# PS_TPS54340_Voltage_CurrentRev2_1.net
KiCad netlist of a schematic drawn in EAGLE
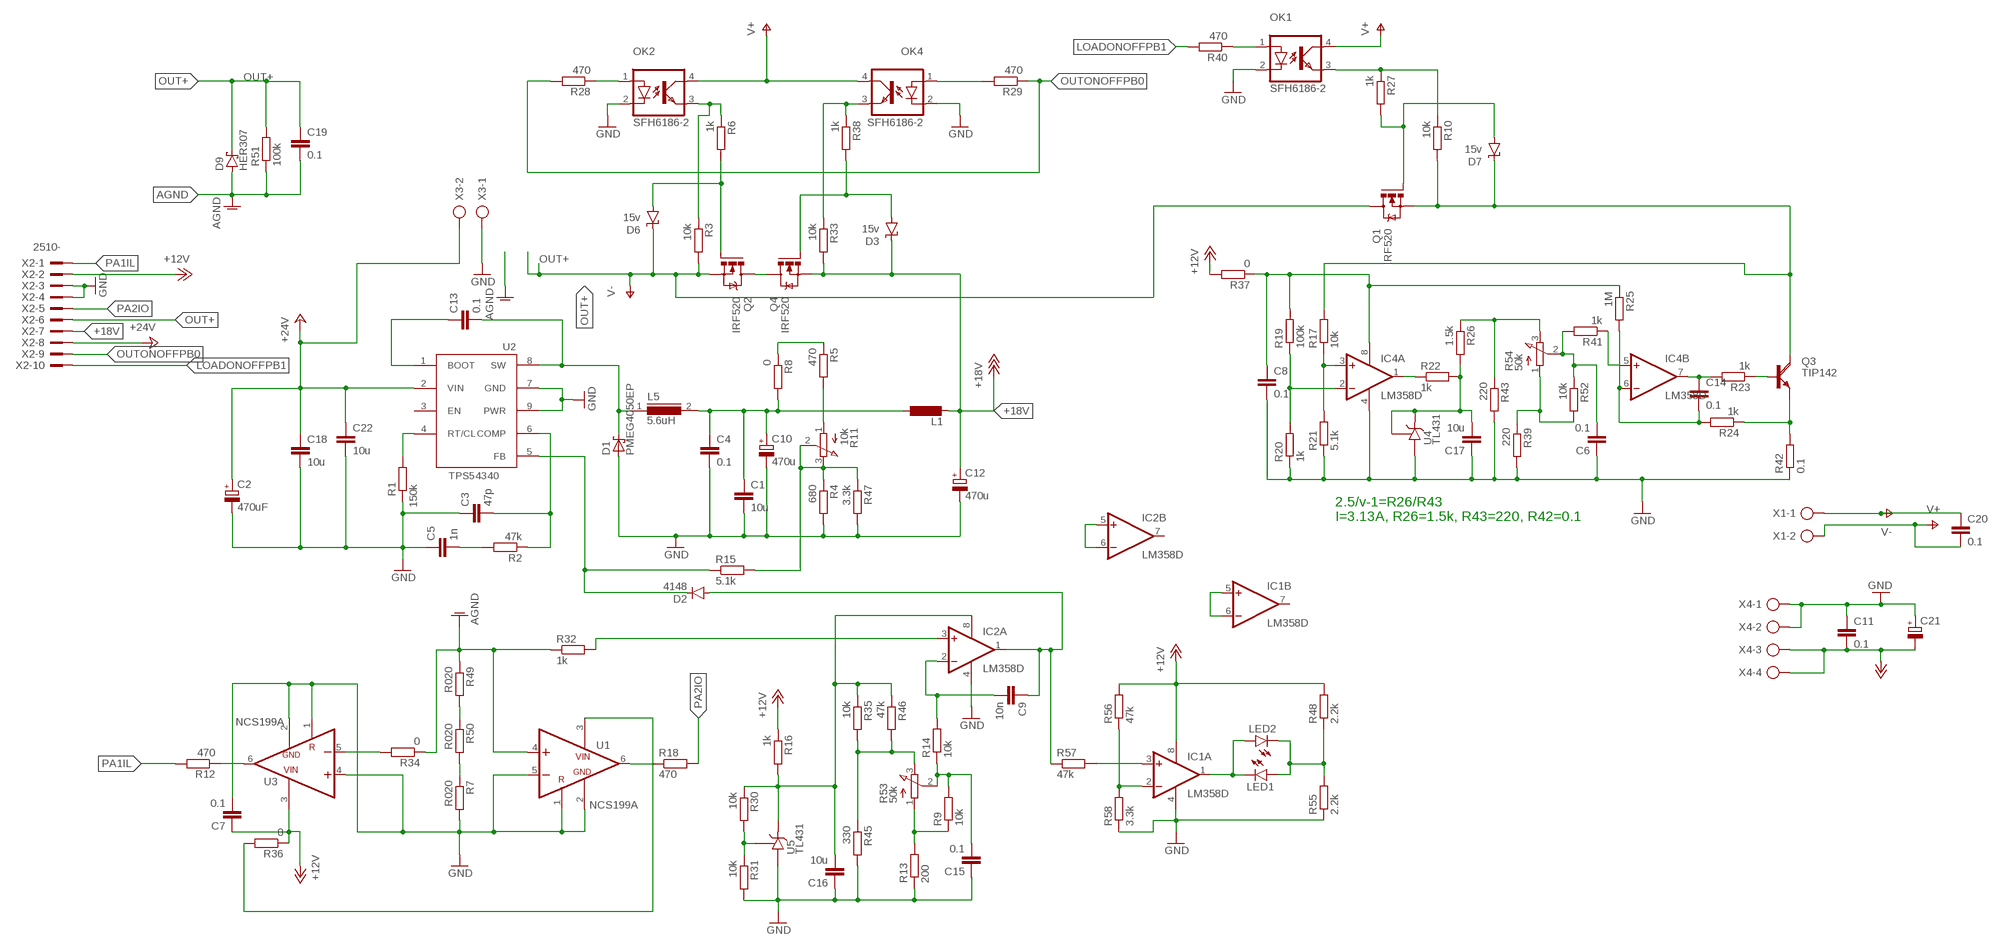
[diagram p0: schematic, sheet 1]

(export (version "E")
  (design (tool "Eeschema 10.0.6"))
  (components
    (comp (ref "C1")
      (value "10u")
      (footprint "eagle-import:C1210")
      (libsource (lib "eagle-import") (part "rcl_334_C-EUC1210"))
    )
    (comp (ref "C2")
      (value "470uF")
      (footprint "eagle-import:E5-10,5")
      (libsource (lib "eagle-import") (part "CPOL-EUE5-10.5"))
    )
    (comp (ref "C3")
      (value "47p")
      (footprint "eagle-import:C0603K")
      (libsource (lib "eagle-import") (part "rcl_334_C-EUC0603K"))
    )
    (comp (ref "C4")
      (value "0.1")
      (footprint "eagle-import:C1206")
      (libsource (lib "eagle-import") (part "C-EUC1206"))
    )
    (comp (ref "C5")
      (value "1n")
      (footprint "eagle-import:C0603K")
      (libsource (lib "eagle-import") (part "rcl_334_C-EUC0603K"))
    )
    (comp (ref "C6")
      (value "0.1")
      (footprint "eagle-import:C0603K")
      (libsource (lib "eagle-import") (part "rcl_334_C-EUC0603K"))
    )
    (comp (ref "C7")
      (value "0.1")
      (footprint "eagle-import:C0603K")
      (libsource (lib "eagle-import") (part "rcl_334_C-EUC0603K"))
    )
    (comp (ref "C8")
      (value "0.1")
      (footprint "eagle-import:C1206")
      (libsource (lib "eagle-import") (part "C-EUC1206"))
    )
    (comp (ref "C9")
      (value "10n")
      (footprint "eagle-import:C0603K")
      (libsource (lib "eagle-import") (part "rcl_334_C-EUC0603K"))
    )
    (comp (ref "C10")
      (value "470u")
      (footprint "eagle-import:E5-10,5")
      (libsource (lib "eagle-import") (part "CPOL-EUE5-10.5"))
    )
    (comp (ref "C11")
      (value "0.1")
      (footprint "eagle-import:C1206")
      (libsource (lib "eagle-import") (part "C-EUC1206"))
    )
    (comp (ref "C12")
      (value "470u")
      (footprint "eagle-import:E5-10,5")
      (libsource (lib "eagle-import") (part "CPOL-EUE5-10.5"))
    )
    (comp (ref "C13")
      (value "0.1")
      (footprint "eagle-import:C102-043X133")
      (libsource (lib "eagle-import") (part "rcl_334_C-EU102-043X133"))
    )
    (comp (ref "C14")
      (value "0.1")
      (footprint "eagle-import:C1206")
      (libsource (lib "eagle-import") (part "C-EUC1206"))
    )
    (comp (ref "C15")
      (value "0.1")
      (footprint "eagle-import:C0603K")
      (libsource (lib "eagle-import") (part "rcl_334_C-EUC0603K"))
    )
    (comp (ref "C16")
      (value "10u")
      (footprint "eagle-import:C0603K")
      (libsource (lib "eagle-import") (part "rcl_334_C-EUC0603K"))
    )
    (comp (ref "C17")
      (value "10u")
      (footprint "eagle-import:C0603K")
      (libsource (lib "eagle-import") (part "rcl_334_C-EUC0603K"))
    )
    (comp (ref "C18")
      (value "10u")
      (footprint "eagle-import:C1210")
      (libsource (lib "eagle-import") (part "rcl_334_C-EUC1210"))
    )
    (comp (ref "C19")
      (value "0.1")
      (footprint "eagle-import:C150-054X183")
      (libsource (lib "eagle-import") (part "rcl_334_C-EU150-054X183"))
    )
    (comp (ref "C20")
      (value "0.1")
      (footprint "eagle-import:C1206")
      (libsource (lib "eagle-import") (part "C-EUC1206"))
    )
    (comp (ref "C21")
      (value "CPOL-EUE2.5-6")
      (footprint "eagle-import:E2,5-6")
      (libsource (lib "eagle-import") (part "CPOL-EUE2.5-6"))
    )
    (comp (ref "C22")
      (value "10u")
      (footprint "eagle-import:C1210")
      (libsource (lib "eagle-import") (part "rcl_334_C-EUC1210"))
    )
    (comp (ref "D1")
      (value "PMEG4050EP")
      (footprint "eagle-import:SOD128")
      (libsource (lib "eagle-import") (part "PMEG4050EP"))
    )
    (comp (ref "D2")
      (value "4148")
      (footprint "eagle-import:SOD80C")
      (libsource (lib "eagle-import") (part "PMLL41SOD80C"))
    )
    (comp (ref "D3")
      (value "15v")
      (footprint "eagle-import:SMBJ")
      (libsource (lib "eagle-import") (part "SUPPRESSOR-SMBJ"))
    )
    (comp (ref "D6")
      (value "15v")
      (footprint "eagle-import:SMBJ")
      (libsource (lib "eagle-import") (part "SUPPRESSOR-SMBJ"))
    )
    (comp (ref "D7")
      (value "15v")
      (footprint "eagle-import:SMBJ")
      (libsource (lib "eagle-import") (part "SUPPRESSOR-SMBJ"))
    )
    (comp (ref "D9")
      (value "HER307")
      (footprint "eagle-import:CB429-17")
      (libsource (lib "eagle-import") (part "15KEXX"))
    )
    (comp (ref "IC1")
      (value "LM358D")
      (footprint "eagle-import:SO08")
      (libsource (lib "eagle-import") (part "LM358D"))
    )
    (comp (ref "IC2")
      (value "LM358D")
      (footprint "eagle-import:SO08")
      (libsource (lib "eagle-import") (part "LM358D"))
    )
    (comp (ref "IC4")
      (value "LM358D")
      (footprint "eagle-import:SO08")
      (libsource (lib "eagle-import") (part "LM358D"))
    )
    (comp (ref "L1")
      (value "L-EU0207/5V")
      (footprint "eagle-import:0207_5V")
      (libsource (lib "eagle-import") (part "L-EU0207/5V"))
    )
    (comp (ref "L5")
      (value "5.6uH")
      (footprint "eagle-import:DR125")
      (libsource (lib "eagle-import") (part "DR125"))
    )
    (comp (ref "LED1")
      (value "LEDB152")
      (footprint "eagle-import:Q62902-B152")
      (libsource (lib "eagle-import") (part "LEDB152"))
    )
    (comp (ref "LED2")
      (value "LEDB152")
      (footprint "eagle-import:Q62902-B152")
      (libsource (lib "eagle-import") (part "LEDB152"))
    )
    (comp (ref "OK1")
      (value "SFH6186-2")
      (footprint "eagle-import:SMD4-7")
      (fields (field (name "MF") "VISHAY/TELEFUNKEN"))
      (libsource (lib "eagle-import") (part "SFH618?6-2"))
    )
    (comp (ref "OK2")
      (value "SFH6186-2")
      (footprint "eagle-import:SMD4-7")
      (fields (field (name "MF") "VISHAY/TELEFUNKEN"))
      (libsource (lib "eagle-import") (part "SFH618?6-2"))
    )
    (comp (ref "OK4")
      (value "SFH6186-2")
      (footprint "eagle-import:SMD4-7")
      (fields (field (name "MF") "VISHAY/TELEFUNKEN"))
      (libsource (lib "eagle-import") (part "SFH618?6-2"))
    )
    (comp (ref "Q1")
      (value "IRF520")
      (footprint "eagle-import:TO220BV")
      (libsource (lib "eagle-import") (part "IRF520"))
    )
    (comp (ref "Q2")
      (value "IRF520")
      (footprint "eagle-import:TO220BV")
      (libsource (lib "eagle-import") (part "IRF520"))
    )
    (comp (ref "Q3")
      (value "TIP142")
      (footprint "eagle-import:SOT93")
      (libsource (lib "eagle-import") (part "TIP142"))
    )
    (comp (ref "Q4")
      (value "IRF520")
      (footprint "eagle-import:TO220BV")
      (libsource (lib "eagle-import") (part "IRF520"))
    )
    (comp (ref "R1")
      (value "150k")
      (footprint "eagle-import:R1206")
      (libsource (lib "eagle-import") (part "R-EU_R1206"))
    )
    (comp (ref "R2")
      (value "47k")
      (footprint "eagle-import:R0603")
      (libsource (lib "eagle-import") (part "rcl_334_R-EU_R0603"))
    )
    (comp (ref "R3")
      (value "10k")
      (footprint "eagle-import:R0603")
      (libsource (lib "eagle-import") (part "rcl_334_R-EU_R0603"))
    )
    (comp (ref "R4")
      (value "680")
      (footprint "eagle-import:R1206")
      (libsource (lib "eagle-import") (part "R-EU_R1206"))
    )
    (comp (ref "R5")
      (value "470")
      (footprint "eagle-import:R1206")
      (libsource (lib "eagle-import") (part "R-EU_R1206"))
    )
    (comp (ref "R6")
      (value "1k")
      (footprint "eagle-import:R0603")
      (libsource (lib "eagle-import") (part "rcl_334_R-EU_R0603"))
    )
    (comp (ref "R7")
      (value "R020")
      (footprint "eagle-import:R1206")
      (libsource (lib "eagle-import") (part "R-EU_R1206"))
    )
    (comp (ref "R8")
      (value "0")
      (footprint "eagle-import:R0603")
      (libsource (lib "eagle-import") (part "rcl_334_R-EU_R0603"))
    )
    (comp (ref "R9")
      (value "10k")
      (footprint "eagle-import:R0603")
      (libsource (lib "eagle-import") (part "rcl_334_R-EU_R0603"))
    )
    (comp (ref "R10")
      (value "10k")
      (footprint "eagle-import:R0603")
      (libsource (lib "eagle-import") (part "rcl_334_R-EU_R0603"))
    )
    (comp (ref "R11")
      (value "10k")
      (footprint "eagle-import:3RP_1610N")
      (libsource (lib "eagle-import") (part "3RP/1610N"))
    )
    (comp (ref "R12")
      (value "470")
      (footprint "eagle-import:R0603")
      (libsource (lib "eagle-import") (part "rcl_334_R-EU_R0603"))
    )
    (comp (ref "R13")
      (value "200")
      (footprint "eagle-import:R0603")
      (libsource (lib "eagle-import") (part "rcl_334_R-EU_R0603"))
    )
    (comp (ref "R14")
      (value "10k")
      (footprint "eagle-import:R1206")
      (libsource (lib "eagle-import") (part "R-EU_R1206"))
    )
    (comp (ref "R15")
      (value "5.1k")
      (footprint "eagle-import:R0603")
      (libsource (lib "eagle-import") (part "rcl_334_R-EU_R0603"))
    )
    (comp (ref "R16")
      (value "1k")
      (footprint "eagle-import:R0603")
      (libsource (lib "eagle-import") (part "rcl_334_R-EU_R0603"))
    )
    (comp (ref "R17")
      (value "10k")
      (footprint "eagle-import:R1206")
      (libsource (lib "eagle-import") (part "R-EU_R1206"))
    )
    (comp (ref "R18")
      (value "470")
      (footprint "eagle-import:R0603")
      (libsource (lib "eagle-import") (part "rcl_334_R-EU_R0603"))
    )
    (comp (ref "R19")
      (value "100k")
      (footprint "eagle-import:R1206")
      (libsource (lib "eagle-import") (part "R-EU_R1206"))
    )
    (comp (ref "R20")
      (value "1k")
      (footprint "eagle-import:R1206")
      (libsource (lib "eagle-import") (part "R-EU_R1206"))
    )
    (comp (ref "R21")
      (value "5.1k")
      (footprint "eagle-import:R1206")
      (libsource (lib "eagle-import") (part "R-EU_R1206"))
    )
    (comp (ref "R22")
      (value "1k")
      (footprint "eagle-import:R0603")
      (libsource (lib "eagle-import") (part "rcl_334_R-EU_R0603"))
    )
    (comp (ref "R23")
      (value "1k")
      (footprint "eagle-import:R1206")
      (libsource (lib "eagle-import") (part "R-EU_R1206"))
    )
    (comp (ref "R24")
      (value "1k")
      (footprint "eagle-import:R1206")
      (libsource (lib "eagle-import") (part "R-EU_R1206"))
    )
    (comp (ref "R25")
      (value "1M")
      (footprint "eagle-import:R1206")
      (libsource (lib "eagle-import") (part "R-EU_R1206"))
    )
    (comp (ref "R26")
      (value "1.5k")
      (footprint "eagle-import:R0603")
      (libsource (lib "eagle-import") (part "rcl_334_R-EU_R0603"))
    )
    (comp (ref "R27")
      (value "1k")
      (footprint "eagle-import:R0603")
      (libsource (lib "eagle-import") (part "rcl_334_R-EU_R0603"))
    )
    (comp (ref "R28")
      (value "470")
      (footprint "eagle-import:R0603")
      (libsource (lib "eagle-import") (part "rcl_334_R-EU_R0603"))
    )
    (comp (ref "R29")
      (value "470")
      (footprint "eagle-import:R0603")
      (libsource (lib "eagle-import") (part "rcl_334_R-EU_R0603"))
    )
    (comp (ref "R30")
      (value "10k")
      (footprint "eagle-import:R0603")
      (libsource (lib "eagle-import") (part "rcl_334_R-EU_R0603"))
    )
    (comp (ref "R31")
      (value "10k")
      (footprint "eagle-import:R0603")
      (libsource (lib "eagle-import") (part "rcl_334_R-EU_R0603"))
    )
    (comp (ref "R32")
      (value "1k")
      (footprint "eagle-import:R1206")
      (libsource (lib "eagle-import") (part "R-EU_R1206"))
    )
    (comp (ref "R33")
      (value "10k")
      (footprint "eagle-import:R0603")
      (libsource (lib "eagle-import") (part "rcl_334_R-EU_R0603"))
    )
    (comp (ref "R34")
      (value "0")
      (footprint "eagle-import:R1206")
      (libsource (lib "eagle-import") (part "R-EU_R1206"))
    )
    (comp (ref "R35")
      (value "10k")
      (footprint "eagle-import:R0603")
      (libsource (lib "eagle-import") (part "rcl_334_R-EU_R0603"))
    )
    (comp (ref "R36")
      (value "0")
      (footprint "eagle-import:R1206")
      (libsource (lib "eagle-import") (part "R-EU_R1206"))
    )
    (comp (ref "R37")
      (value "0")
      (footprint "eagle-import:R1206")
      (libsource (lib "eagle-import") (part "R-EU_R1206"))
    )
    (comp (ref "R38")
      (value "1k")
      (footprint "eagle-import:R0603")
      (libsource (lib "eagle-import") (part "rcl_334_R-EU_R0603"))
    )
    (comp (ref "R39")
      (value "220")
      (footprint "eagle-import:R0603")
      (libsource (lib "eagle-import") (part "rcl_334_R-EU_R0603"))
    )
    (comp (ref "R40")
      (value "470")
      (footprint "eagle-import:R0603")
      (libsource (lib "eagle-import") (part "rcl_334_R-EU_R0603"))
    )
    (comp (ref "R41")
      (value "1k")
      (footprint "eagle-import:R1206")
      (libsource (lib "eagle-import") (part "R-EU_R1206"))
    )
    (comp (ref "R42")
      (value "0.1")
      (footprint "eagle-import:0414_15")
      (libsource (lib "eagle-import") (part "rcl_334_R-EU_0414/15"))
    )
    (comp (ref "R43")
      (value "220")
      (footprint "eagle-import:R0603")
      (libsource (lib "eagle-import") (part "rcl_334_R-EU_R0603"))
    )
    (comp (ref "R45")
      (value "330")
      (footprint "eagle-import:R0603")
      (libsource (lib "eagle-import") (part "rcl_334_R-EU_R0603"))
    )
    (comp (ref "R46")
      (value "47k")
      (footprint "eagle-import:R0603")
      (libsource (lib "eagle-import") (part "rcl_334_R-EU_R0603"))
    )
    (comp (ref "R47")
      (value "3.3k")
      (footprint "eagle-import:R1206")
      (libsource (lib "eagle-import") (part "R-EU_R1206"))
    )
    (comp (ref "R48")
      (value "2.2k")
      (footprint "eagle-import:R0603")
      (libsource (lib "eagle-import") (part "rcl_334_R-EU_R0603"))
    )
    (comp (ref "R49")
      (value "R020")
      (footprint "eagle-import:R1206")
      (libsource (lib "eagle-import") (part "R-EU_R1206"))
    )
    (comp (ref "R50")
      (value "R020")
      (footprint "eagle-import:R1206")
      (libsource (lib "eagle-import") (part "R-EU_R1206"))
    )
    (comp (ref "R51")
      (value "100k")
      (footprint "eagle-import:0207_15")
      (libsource (lib "eagle-import") (part "rcl_334_R-EU_0207/15"))
    )
    (comp (ref "R52")
      (value "10k")
      (footprint "eagle-import:R0603")
      (libsource (lib "eagle-import") (part "rcl_334_R-EU_R0603"))
    )
    (comp (ref "R53")
      (value "50k")
      (footprint "eagle-import:3RP_1610N")
      (libsource (lib "eagle-import") (part "3RP/1610N"))
    )
    (comp (ref "R54")
      (value "50k")
      (footprint "eagle-import:3RP_1610N")
      (libsource (lib "eagle-import") (part "3RP/1610N"))
    )
    (comp (ref "R55")
      (value "2.2k")
      (footprint "eagle-import:R0603")
      (libsource (lib "eagle-import") (part "rcl_334_R-EU_R0603"))
    )
    (comp (ref "R56")
      (value "47k")
      (footprint "eagle-import:R0603")
      (libsource (lib "eagle-import") (part "rcl_334_R-EU_R0603"))
    )
    (comp (ref "R57")
      (value "47k")
      (footprint "eagle-import:R0603")
      (libsource (lib "eagle-import") (part "rcl_334_R-EU_R0603"))
    )
    (comp (ref "R58")
      (value "3.3k")
      (footprint "eagle-import:R0603")
      (libsource (lib "eagle-import") (part "rcl_334_R-EU_R0603"))
    )
    (comp (ref "U1")
      (value "NCS199A")
      (footprint "eagle-import:SOT363")
      (libsource (lib "eagle-import") (part "NCS199A"))
    )
    (comp (ref "U2")
      (value "TPS54340")
      (footprint "eagle-import:HSOP")
      (libsource (lib "eagle-import") (part "TPS54340SO8"))
    )
    (comp (ref "U3")
      (value "NCS199A")
      (footprint "eagle-import:SOT363")
      (libsource (lib "eagle-import") (part "NCS199A"))
    )
    (comp (ref "U4")
      (value "TL431")
      (footprint "eagle-import:SOT23")
      (libsource (lib "eagle-import") (part "TL431"))
    )
    (comp (ref "U5")
      (value "TL431")
      (footprint "eagle-import:SOT23")
      (libsource (lib "eagle-import") (part "TL431"))
    )
    (comp (ref "X1")
      (value "AK500/2")
      (footprint "eagle-import:AK500_2")
      (libsource (lib "eagle-import") (part "AK500/2"))
    )
    (comp (ref "X2")
      (value "2510-")
      (footprint "eagle-import:PAK100_2500-10")
      (fields (field (name "MF") "3M") (field (name "MPN") "2510-6002UB"))
      (libsource (lib "eagle-import") (part "2510-"))
    )
    (comp (ref "X3")
      (value "AK500/2")
      (footprint "eagle-import:AK500_2")
      (libsource (lib "eagle-import") (part "AK500/2"))
    )
    (comp (ref "X4")
      (value "AK500/4")
      (footprint "eagle-import:AK500_4")
      (libsource (lib "eagle-import") (part "AK500/4"))
    )
  )
  (nets
    (net (code "1") (name "+12V") (class "Default")
      (node (ref "C11") (pin "2") (pinfunction "2_2") (pintype "passive"))
      (node (ref "C21") (pin "-") (pinfunction "-_-") (pintype "passive"))
      (node (ref "C7") (pin "1") (pinfunction "1_1") (pintype "passive"))
      (node (ref "IC1") (pin "8") (pinfunction "V+_8") (pintype "power_in"))
      (node (ref "R16") (pin "1") (pinfunction "1_1") (pintype "passive"))
      (node (ref "R36") (pin "1") (pinfunction "1_1") (pintype "passive"))
      (node (ref "R37") (pin "2") (pinfunction "2_2") (pintype "passive"))
      (node (ref "R48") (pin "2") (pinfunction "2_2") (pintype "passive"))
      (node (ref "R56") (pin "2") (pinfunction "2_2") (pintype "passive"))
      (node (ref "U3") (pin "3") (pinfunction "VCC_3") (pintype "power_in"))
      (node (ref "X2") (pin "2") (pinfunction "KL_2") (pintype "passive"))
      (node (ref "X4") (pin "3") (pinfunction "KL_3") (pintype "passive"))
      (node (ref "X4") (pin "4") (pinfunction "KL_4") (pintype "passive"))
    )
    (net (code "2") (name "+18V") (class "Default")
      (node (ref "C12") (pin "+") (pinfunction "+_+") (pintype "passive"))
      (node (ref "D3") (pin "C") (pinfunction "C_C") (pintype "passive"))
      (node (ref "L1") (pin "2") (pinfunction "2_2") (pintype "passive"))
      (node (ref "Q4") (pin "S") (pinfunction "S_S") (pintype "passive"))
      (node (ref "R33") (pin "2") (pinfunction "2_2") (pintype "passive"))
      (node (ref "X2") (pin "7") (pinfunction "KL_7") (pintype "passive"))
    )
    (net (code "3") (name "+24V") (class "Default")
      (node (ref "C18") (pin "1") (pinfunction "1_1") (pintype "passive"))
      (node (ref "C2") (pin "+") (pinfunction "+_+") (pintype "passive"))
      (node (ref "C22") (pin "1") (pinfunction "1_1") (pintype "passive"))
      (node (ref "U2") (pin "2") (pinfunction "VIN_2") (pintype "power_in"))
      (node (ref "X2") (pin "8") (pinfunction "KL_8") (pintype "passive"))
      (node (ref "X3") (pin "2") (pinfunction "KL_2") (pintype "passive"))
    )
    (net (code "4") (name "AGND") (class "Default")
      (node (ref "C19") (pin "2") (pinfunction "2_2") (pintype "passive"))
      (node (ref "D9") (pin "A") (pinfunction "A_A") (pintype "passive"))
      (node (ref "R32") (pin "1") (pinfunction "1_1") (pintype "passive"))
      (node (ref "R34") (pin "1") (pinfunction "1_1") (pintype "passive"))
      (node (ref "R49") (pin "1") (pinfunction "1_1") (pintype "passive"))
      (node (ref "R51") (pin "1") (pinfunction "1_1") (pintype "passive"))
      (node (ref "U1") (pin "4") (pinfunction "IN+_4") (pintype "input"))
    )
    (net (code "5") (name "GND") (class "Default")
      (node (ref "C1") (pin "2") (pinfunction "2_2") (pintype "passive"))
      (node (ref "C10") (pin "-") (pinfunction "-_-") (pintype "passive"))
      (node (ref "C11") (pin "1") (pinfunction "1_1") (pintype "passive"))
      (node (ref "C12") (pin "-") (pinfunction "-_-") (pintype "passive"))
      (node (ref "C15") (pin "1") (pinfunction "1_1") (pintype "passive"))
      (node (ref "C16") (pin "1") (pinfunction "1_1") (pintype "passive"))
      (node (ref "C17") (pin "1") (pinfunction "1_1") (pintype "passive"))
      (node (ref "C18") (pin "2") (pinfunction "2_2") (pintype "passive"))
      (node (ref "C2") (pin "-") (pinfunction "-_-") (pintype "passive"))
      (node (ref "C21") (pin "+") (pinfunction "+_+") (pintype "passive"))
      (node (ref "C22") (pin "2") (pinfunction "2_2") (pintype "passive"))
      (node (ref "C3") (pin "1") (pinfunction "1_1") (pintype "passive"))
      (node (ref "C4") (pin "2") (pinfunction "2_2") (pintype "passive"))
      (node (ref "C5") (pin "1") (pinfunction "1_1") (pintype "passive"))
      (node (ref "C6") (pin "1") (pinfunction "1_1") (pintype "passive"))
      (node (ref "C7") (pin "2") (pinfunction "2_2") (pintype "passive"))
      (node (ref "C8") (pin "2") (pinfunction "2_2") (pintype "passive"))
      (node (ref "D1") (pin "2") (pinfunction "A_2") (pintype "passive"))
      (node (ref "IC1") (pin "4") (pinfunction "V-_4") (pintype "power_in"))
      (node (ref "IC2") (pin "4") (pinfunction "V-_4") (pintype "power_in"))
      (node (ref "IC4") (pin "4") (pinfunction "V-_4") (pintype "power_in"))
      (node (ref "OK1") (pin "2") (pinfunction "C_2") (pintype "passive"))
      (node (ref "OK2") (pin "2") (pinfunction "C_2") (pintype "passive"))
      (node (ref "OK4") (pin "2") (pinfunction "C_2") (pintype "passive"))
      (node (ref "R1") (pin "1") (pinfunction "1_1") (pintype "passive"))
      (node (ref "R13") (pin "1") (pinfunction "1_1") (pintype "passive"))
      (node (ref "R20") (pin "1") (pinfunction "1_1") (pintype "passive"))
      (node (ref "R21") (pin "1") (pinfunction "1_1") (pintype "passive"))
      (node (ref "R31") (pin "2") (pinfunction "2_2") (pintype "passive"))
      (node (ref "R39") (pin "2") (pinfunction "2_2") (pintype "passive"))
      (node (ref "R4") (pin "2") (pinfunction "2_2") (pintype "passive"))
      (node (ref "R42") (pin "1") (pinfunction "1_1") (pintype "passive"))
      (node (ref "R43") (pin "2") (pinfunction "2_2") (pintype "passive"))
      (node (ref "R45") (pin "2") (pinfunction "2_2") (pintype "passive"))
      (node (ref "R47") (pin "2") (pinfunction "2_2") (pintype "passive"))
      (node (ref "R55") (pin "1") (pinfunction "1_1") (pintype "passive"))
      (node (ref "R58") (pin "1") (pinfunction "1_1") (pintype "passive"))
      (node (ref "R7") (pin "2") (pinfunction "2_2") (pintype "passive"))
      (node (ref "U1") (pin "1") (pinfunction "REF_1") (pintype "input"))
      (node (ref "U1") (pin "2") (pinfunction "GND_2") (pintype "power_in"))
      (node (ref "U1") (pin "5") (pinfunction "IN-_5") (pintype "input"))
      (node (ref "U2") (pin "7") (pinfunction "GND_7") (pintype "power_in"))
      (node (ref "U2") (pin "9") (pinfunction "PWR_9") (pintype "power_in"))
      (node (ref "U3") (pin "1") (pinfunction "REF_1") (pintype "input"))
      (node (ref "U3") (pin "2") (pinfunction "GND_2") (pintype "power_in"))
      (node (ref "U3") (pin "4") (pinfunction "IN+_4") (pintype "input"))
      (node (ref "U4") (pin "3") (pinfunction "A_3") (pintype "passive"))
      (node (ref "U5") (pin "3") (pinfunction "A_3") (pintype "passive"))
      (node (ref "X2") (pin "3") (pinfunction "KL_3") (pintype "passive"))
      (node (ref "X2") (pin "4") (pinfunction "KL_4") (pintype "passive"))
      (node (ref "X3") (pin "1") (pinfunction "KL_1") (pintype "passive"))
      (node (ref "X4") (pin "1") (pinfunction "KL_1") (pintype "passive"))
      (node (ref "X4") (pin "2") (pinfunction "KL_2") (pintype "passive"))
    )
    (net (code "6") (name "LOADONOFFPB1") (class "Default")
      (node (ref "R40") (pin "2") (pinfunction "2_2") (pintype "passive"))
      (node (ref "X2") (pin "10") (pinfunction "KL_10") (pintype "passive"))
    )
    (net (code "7") (name "Net-(C1-Pad1)") (class "Default")
      (node (ref "C1") (pin "1") (pinfunction "1_1") (pintype "passive"))
      (node (ref "C10") (pin "+") (pinfunction "+_+") (pintype "passive"))
      (node (ref "C4") (pin "1") (pinfunction "1_1") (pintype "passive"))
      (node (ref "L1") (pin "1") (pinfunction "1_1") (pintype "passive"))
      (node (ref "L5") (pin "2") (pinfunction "2_2") (pintype "passive"))
      (node (ref "R8") (pin "2") (pinfunction "2_2") (pintype "passive"))
    )
    (net (code "8") (name "Net-(C5-Pad2)") (class "Default")
      (node (ref "C5") (pin "2") (pinfunction "2_2") (pintype "passive"))
      (node (ref "R2") (pin "2") (pinfunction "2_2") (pintype "passive"))
    )
    (net (code "9") (name "Net-(D1-K)") (class "Default")
      (node (ref "C13") (pin "2") (pinfunction "2_2") (pintype "passive"))
      (node (ref "D1") (pin "1") (pinfunction "K_1") (pintype "passive"))
      (node (ref "L5") (pin "1") (pinfunction "1_1") (pintype "passive"))
      (node (ref "U2") (pin "8") (pinfunction "SW_8") (pintype "power_in"))
    )
    (net (code "10") (name "Net-(D3-PadA)") (class "Default")
      (node (ref "D3") (pin "A") (pinfunction "A_A") (pintype "passive"))
      (node (ref "Q4") (pin "G") (pinfunction "G_G") (pintype "passive"))
      (node (ref "R38") (pin "2") (pinfunction "2_2") (pintype "passive"))
    )
    (net (code "11") (name "Net-(D6-PadA)") (class "Default")
      (node (ref "D6") (pin "A") (pinfunction "A_A") (pintype "passive"))
      (node (ref "Q2") (pin "G") (pinfunction "G_G") (pintype "passive"))
      (node (ref "R6") (pin "2") (pinfunction "2_2") (pintype "passive"))
    )
    (net (code "12") (name "Net-(D7-PadA)") (class "Default")
      (node (ref "D7") (pin "A") (pinfunction "A_A") (pintype "passive"))
      (node (ref "Q1") (pin "G") (pinfunction "G_G") (pintype "passive"))
      (node (ref "R27") (pin "2") (pinfunction "2_2") (pintype "passive"))
    )
    (net (code "13") (name "Net-(D7-PadC)") (class "Default")
      (node (ref "D7") (pin "C") (pinfunction "C_C") (pintype "passive"))
      (node (ref "Q1") (pin "S") (pinfunction "S_S") (pintype "passive"))
      (node (ref "Q3") (pin "C") (pinfunction "C_C") (pintype "passive"))
      (node (ref "R10") (pin "2") (pinfunction "2_2") (pintype "passive"))
      (node (ref "R17") (pin "2") (pinfunction "2_2") (pintype "passive"))
    )
    (net (code "14") (name "Net-(IC1A-+IN)") (class "Default")
      (node (ref "IC1") (pin "3") (pinfunction "+IN_3") (pintype "input"))
      (node (ref "R57") (pin "2") (pinfunction "2_2") (pintype "passive"))
    )
    (net (code "15") (name "Net-(IC1A--IN)") (class "Default")
      (node (ref "IC1") (pin "2") (pinfunction "-IN_2") (pintype "input"))
      (node (ref "R56") (pin "1") (pinfunction "1_1") (pintype "passive"))
      (node (ref "R58") (pin "2") (pinfunction "2_2") (pintype "passive"))
    )
    (net (code "16") (name "Net-(IC1A-OUT)") (class "Default")
      (node (ref "IC1") (pin "1") (pinfunction "OUT_1") (pintype "output"))
      (node (ref "LED1") (pin "K") (pinfunction "C_K") (pintype "passive"))
      (node (ref "LED2") (pin "A") (pinfunction "A_A") (pintype "passive"))
    )
    (net (code "17") (name "Net-(IC1B-+IN)") (class "Default")
      (node (ref "IC1") (pin "5") (pinfunction "+IN_5") (pintype "input"))
      (node (ref "IC1") (pin "6") (pinfunction "-IN_6") (pintype "input"))
    )
    (net (code "18") (name "Net-(IC2A-+IN)") (class "Default")
      (node (ref "IC2") (pin "3") (pinfunction "+IN_3") (pintype "input"))
      (node (ref "R32") (pin "2") (pinfunction "2_2") (pintype "passive"))
    )
    (net (code "19") (name "Net-(IC2A--IN)") (class "Default")
      (node (ref "C9") (pin "2") (pinfunction "2_2") (pintype "passive"))
      (node (ref "IC2") (pin "2") (pinfunction "-IN_2") (pintype "input"))
      (node (ref "R14") (pin "2") (pinfunction "2_2") (pintype "passive"))
    )
    (net (code "20") (name "Net-(IC2A-OUT)") (class "Default")
      (node (ref "C9") (pin "1") (pinfunction "1_1") (pintype "passive"))
      (node (ref "D2") (pin "A") (pinfunction "A_A") (pintype "passive"))
      (node (ref "IC2") (pin "1") (pinfunction "OUT_1") (pintype "output"))
      (node (ref "R57") (pin "1") (pinfunction "1_1") (pintype "passive"))
    )
    (net (code "21") (name "Net-(IC2B-+IN)") (class "Default")
      (node (ref "IC2") (pin "5") (pinfunction "+IN_5") (pintype "input"))
      (node (ref "IC2") (pin "6") (pinfunction "-IN_6") (pintype "input"))
    )
    (net (code "22") (name "Net-(IC2C-V+)") (class "Default")
      (node (ref "C16") (pin "2") (pinfunction "2_2") (pintype "passive"))
      (node (ref "IC2") (pin "8") (pinfunction "V+_8") (pintype "power_in"))
      (node (ref "R16") (pin "2") (pinfunction "2_2") (pintype "passive"))
      (node (ref "R30") (pin "1") (pinfunction "1_1") (pintype "passive"))
      (node (ref "R35") (pin "1") (pinfunction "1_1") (pintype "passive"))
      (node (ref "R46") (pin "1") (pinfunction "1_1") (pintype "passive"))
      (node (ref "U5") (pin "1") (pinfunction "C_1") (pintype "passive"))
    )
    (net (code "23") (name "Net-(IC4A-+IN)") (class "Default")
      (node (ref "IC4") (pin "3") (pinfunction "+IN_3") (pintype "input"))
      (node (ref "R17") (pin "1") (pinfunction "1_1") (pintype "passive"))
      (node (ref "R21") (pin "2") (pinfunction "2_2") (pintype "passive"))
    )
    (net (code "24") (name "Net-(IC4A--IN)") (class "Default")
      (node (ref "IC4") (pin "2") (pinfunction "-IN_2") (pintype "input"))
      (node (ref "R19") (pin "1") (pinfunction "1_1") (pintype "passive"))
      (node (ref "R20") (pin "2") (pinfunction "2_2") (pintype "passive"))
    )
    (net (code "25") (name "Net-(IC4A-OUT)") (class "Default")
      (node (ref "IC4") (pin "1") (pinfunction "OUT_1") (pintype "output"))
      (node (ref "R22") (pin "1") (pinfunction "1_1") (pintype "passive"))
    )
    (net (code "26") (name "Net-(IC4B-+IN)") (class "Default")
      (node (ref "IC4") (pin "5") (pinfunction "+IN_5") (pintype "input"))
      (node (ref "R41") (pin "1") (pinfunction "1_1") (pintype "passive"))
    )
    (net (code "27") (name "Net-(IC4B--IN)") (class "Default")
      (node (ref "C14") (pin "2") (pinfunction "2_2") (pintype "passive"))
      (node (ref "IC4") (pin "6") (pinfunction "-IN_6") (pintype "input"))
      (node (ref "R24") (pin "2") (pinfunction "2_2") (pintype "passive"))
      (node (ref "R25") (pin "2") (pinfunction "2_2") (pintype "passive"))
    )
    (net (code "28") (name "Net-(IC4B-OUT)") (class "Default")
      (node (ref "C14") (pin "1") (pinfunction "1_1") (pintype "passive"))
      (node (ref "IC4") (pin "7") (pinfunction "OUT_7") (pintype "output"))
      (node (ref "R23") (pin "2") (pinfunction "2_2") (pintype "passive"))
    )
    (net (code "29") (name "Net-(IC4C-V+)") (class "Default")
      (node (ref "C8") (pin "1") (pinfunction "1_1") (pintype "passive"))
      (node (ref "IC4") (pin "8") (pinfunction "V+_8") (pintype "power_in"))
      (node (ref "R19") (pin "2") (pinfunction "2_2") (pintype "passive"))
      (node (ref "R25") (pin "1") (pinfunction "1_1") (pintype "passive"))
      (node (ref "R37") (pin "1") (pinfunction "1_1") (pintype "passive"))
    )
    (net (code "30") (name "Net-(LED2-C)") (class "Default")
      (node (ref "LED1") (pin "A") (pinfunction "A_A") (pintype "passive"))
      (node (ref "LED2") (pin "K") (pinfunction "C_K") (pintype "passive"))
      (node (ref "R48") (pin "1") (pinfunction "1_1") (pintype "passive"))
      (node (ref "R55") (pin "2") (pinfunction "2_2") (pintype "passive"))
    )
    (net (code "31") (name "Net-(OK1-A)") (class "Default")
      (node (ref "OK1") (pin "1") (pinfunction "A_1") (pintype "passive"))
      (node (ref "R40") (pin "1") (pinfunction "1_1") (pintype "passive"))
    )
    (net (code "32") (name "Net-(OK1-EMIT)") (class "Default")
      (node (ref "OK1") (pin "3") (pinfunction "EMIT_3") (pintype "passive"))
      (node (ref "R10") (pin "1") (pinfunction "1_1") (pintype "passive"))
      (node (ref "R27") (pin "1") (pinfunction "1_1") (pintype "passive"))
    )
    (net (code "33") (name "Net-(OK2-A)") (class "Default")
      (node (ref "OK2") (pin "1") (pinfunction "A_1") (pintype "passive"))
      (node (ref "R28") (pin "1") (pinfunction "1_1") (pintype "passive"))
    )
    (net (code "34") (name "Net-(OK2-EMIT)") (class "Default")
      (node (ref "OK2") (pin "3") (pinfunction "EMIT_3") (pintype "passive"))
      (node (ref "R3") (pin "1") (pinfunction "1_1") (pintype "passive"))
      (node (ref "R6") (pin "1") (pinfunction "1_1") (pintype "passive"))
    )
    (net (code "35") (name "Net-(OK4-A)") (class "Default")
      (node (ref "OK4") (pin "1") (pinfunction "A_1") (pintype "passive"))
      (node (ref "R29") (pin "2") (pinfunction "2_2") (pintype "passive"))
    )
    (net (code "36") (name "Net-(OK4-EMIT)") (class "Default")
      (node (ref "OK4") (pin "3") (pinfunction "EMIT_3") (pintype "passive"))
      (node (ref "R33") (pin "1") (pinfunction "1_1") (pintype "passive"))
      (node (ref "R38") (pin "1") (pinfunction "1_1") (pintype "passive"))
    )
    (net (code "37") (name "Net-(Q2-PadD)") (class "Default")
      (node (ref "Q2") (pin "D") (pinfunction "D_D") (pintype "passive"))
      (node (ref "Q4") (pin "D") (pinfunction "D_D") (pintype "passive"))
    )
    (net (code "38") (name "Net-(Q3-PadB)") (class "Default")
      (node (ref "Q3") (pin "B") (pinfunction "B_B") (pintype "passive"))
      (node (ref "R23") (pin "1") (pinfunction "1_1") (pintype "passive"))
    )
    (net (code "39") (name "Net-(Q3-PadE)") (class "Default")
      (node (ref "Q3") (pin "E") (pinfunction "E_E") (pintype "passive"))
      (node (ref "R24") (pin "1") (pinfunction "1_1") (pintype "passive"))
      (node (ref "R42") (pin "2") (pinfunction "2_2") (pintype "passive"))
    )
    (net (code "40") (name "Net-(R5-Pad1)") (class "Default")
      (node (ref "R5") (pin "1") (pinfunction "1_1") (pintype "passive"))
      (node (ref "R8") (pin "1") (pinfunction "1_1") (pintype "passive"))
    )
    (net (code "41") (name "Net-(R11-A)") (class "Default")
      (node (ref "R11") (pin "1") (pinfunction "A_1") (pintype "passive"))
      (node (ref "R5") (pin "2") (pinfunction "2_2") (pintype "passive"))
    )
    (net (code "42") (name "Net-(R11-E)") (class "Default")
      (node (ref "R11") (pin "2") (pinfunction "S_2") (pintype "passive"))
      (node (ref "R11") (pin "3") (pinfunction "E_3") (pintype "passive"))
      (node (ref "R15") (pin "2") (pinfunction "2_2") (pintype "passive"))
      (node (ref "R4") (pin "1") (pinfunction "1_1") (pintype "passive"))
      (node (ref "R47") (pin "1") (pinfunction "1_1") (pintype "passive"))
    )
    (net (code "43") (name "Net-(R49-Pad2)") (class "Default")
      (node (ref "R49") (pin "2") (pinfunction "2_2") (pintype "passive"))
      (node (ref "R50") (pin "1") (pinfunction "1_1") (pintype "passive"))
    )
    (net (code "44") (name "Net-(R50-Pad2)") (class "Default")
      (node (ref "R50") (pin "2") (pinfunction "2_2") (pintype "passive"))
      (node (ref "R7") (pin "1") (pinfunction "1_1") (pintype "passive"))
    )
    (net (code "45") (name "Net-(R53-A)") (class "Default")
      (node (ref "R13") (pin "2") (pinfunction "2_2") (pintype "passive"))
      (node (ref "R53") (pin "1") (pinfunction "A_1") (pintype "passive"))
      (node (ref "R9") (pin "1") (pinfunction "1_1") (pintype "passive"))
    )
    (net (code "46") (name "Net-(R53-E)") (class "Default")
      (node (ref "R35") (pin "2") (pinfunction "2_2") (pintype "passive"))
      (node (ref "R45") (pin "1") (pinfunction "1_1") (pintype "passive"))
      (node (ref "R46") (pin "2") (pinfunction "2_2") (pintype "passive"))
      (node (ref "R53") (pin "3") (pinfunction "E_3") (pintype "passive"))
    )
    (net (code "47") (name "Net-(R53-S)") (class "Default")
      (node (ref "C15") (pin "2") (pinfunction "2_2") (pintype "passive"))
      (node (ref "R14") (pin "1") (pinfunction "1_1") (pintype "passive"))
      (node (ref "R53") (pin "2") (pinfunction "S_2") (pintype "passive"))
      (node (ref "R9") (pin "2") (pinfunction "2_2") (pintype "passive"))
    )
    (net (code "48") (name "Net-(R54-A)") (class "Default")
      (node (ref "R39") (pin "1") (pinfunction "1_1") (pintype "passive"))
      (node (ref "R52") (pin "2") (pinfunction "2_2") (pintype "passive"))
      (node (ref "R54") (pin "1") (pinfunction "A_1") (pintype "passive"))
    )
    (net (code "49") (name "Net-(R54-E)") (class "Default")
      (node (ref "R26") (pin "1") (pinfunction "1_1") (pintype "passive"))
      (node (ref "R43") (pin "1") (pinfunction "1_1") (pintype "passive"))
      (node (ref "R54") (pin "3") (pinfunction "E_3") (pintype "passive"))
    )
    (net (code "50") (name "Net-(R54-S)") (class "Default")
      (node (ref "C6") (pin "2") (pinfunction "2_2") (pintype "passive"))
      (node (ref "R41") (pin "2") (pinfunction "2_2") (pintype "passive"))
      (node (ref "R52") (pin "1") (pinfunction "1_1") (pintype "passive"))
      (node (ref "R54") (pin "2") (pinfunction "S_2") (pintype "passive"))
    )
    (net (code "51") (name "Net-(U1-OUT)") (class "Default")
      (node (ref "R18") (pin "1") (pinfunction "1_1") (pintype "passive"))
      (node (ref "U1") (pin "6") (pinfunction "OUT_6") (pintype "output"))
    )
    (net (code "52") (name "Net-(U1-VCC)") (class "Default")
      (node (ref "R36") (pin "2") (pinfunction "2_2") (pintype "passive"))
      (node (ref "U1") (pin "3") (pinfunction "VCC_3") (pintype "power_in"))
    )
    (net (code "53") (name "Net-(U2-BOOT)") (class "Default")
      (node (ref "C13") (pin "1") (pinfunction "1_1") (pintype "passive"))
      (node (ref "U2") (pin "1") (pinfunction "BOOT_1") (pintype "input"))
    )
    (net (code "54") (name "Net-(U2-COMP)") (class "Default")
      (node (ref "C3") (pin "2") (pinfunction "2_2") (pintype "passive"))
      (node (ref "R2") (pin "1") (pinfunction "1_1") (pintype "passive"))
      (node (ref "U2") (pin "6") (pinfunction "COMP_6") (pintype "input"))
    )
    (net (code "55") (name "Net-(U2-FB)") (class "Default")
      (node (ref "D2") (pin "C") (pinfunction "C_C") (pintype "passive"))
      (node (ref "R15") (pin "1") (pinfunction "1_1") (pintype "passive"))
      (node (ref "U2") (pin "5") (pinfunction "FB_5") (pintype "input"))
    )
    (net (code "56") (name "Net-(U2-RT{slash}CL)") (class "Default")
      (node (ref "R1") (pin "2") (pinfunction "2_2") (pintype "passive"))
      (node (ref "U2") (pin "4") (pinfunction "RT/CL_4") (pintype "input"))
    )
    (net (code "57") (name "Net-(U3-IN-)") (class "Default")
      (node (ref "R34") (pin "2") (pinfunction "2_2") (pintype "passive"))
      (node (ref "U3") (pin "5") (pinfunction "IN-_5") (pintype "input"))
    )
    (net (code "58") (name "Net-(U3-OUT)") (class "Default")
      (node (ref "R12") (pin "1") (pinfunction "1_1") (pintype "passive"))
      (node (ref "U3") (pin "6") (pinfunction "OUT_6") (pintype "output"))
    )
    (net (code "59") (name "Net-(U4-C)") (class "Default")
      (node (ref "C17") (pin "2") (pinfunction "2_2") (pintype "passive"))
      (node (ref "R22") (pin "2") (pinfunction "2_2") (pintype "passive"))
      (node (ref "R26") (pin "2") (pinfunction "2_2") (pintype "passive"))
      (node (ref "U4") (pin "1") (pinfunction "C_1") (pintype "passive"))
      (node (ref "U4") (pin "2") (pinfunction "R_2") (pintype "passive"))
    )
    (net (code "60") (name "Net-(U5-R)") (class "Default")
      (node (ref "R30") (pin "2") (pinfunction "2_2") (pintype "passive"))
      (node (ref "R31") (pin "1") (pinfunction "1_1") (pintype "passive"))
      (node (ref "U5") (pin "2") (pinfunction "R_2") (pintype "passive"))
    )
    (net (code "61") (name "OUT+") (class "Default")
      (node (ref "C19") (pin "1") (pinfunction "1_1") (pintype "passive"))
      (node (ref "C20") (pin "1") (pinfunction "1_1") (pintype "passive"))
      (node (ref "D6") (pin "C") (pinfunction "C_C") (pintype "passive"))
      (node (ref "D9") (pin "C") (pinfunction "C_C") (pintype "passive"))
      (node (ref "Q1") (pin "D") (pinfunction "D_D") (pintype "passive"))
      (node (ref "Q2") (pin "S") (pinfunction "S_S") (pintype "passive"))
      (node (ref "R3") (pin "2") (pinfunction "2_2") (pintype "passive"))
      (node (ref "R51") (pin "2") (pinfunction "2_2") (pintype "passive"))
      (node (ref "X1") (pin "1") (pinfunction "KL_1") (pintype "passive"))
      (node (ref "X2") (pin "6") (pinfunction "KL_6") (pintype "passive"))
    )
    (net (code "62") (name "OUTONOFFPB0") (class "Default")
      (node (ref "R28") (pin "2") (pinfunction "2_2") (pintype "passive"))
      (node (ref "R29") (pin "1") (pinfunction "1_1") (pintype "passive"))
      (node (ref "X2") (pin "9") (pinfunction "KL_9") (pintype "passive"))
    )
    (net (code "63") (name "PA1IL") (class "Default")
      (node (ref "R12") (pin "2") (pinfunction "2_2") (pintype "passive"))
      (node (ref "X2") (pin "1") (pinfunction "KL_1") (pintype "passive"))
    )
    (net (code "64") (name "PA2IO") (class "Default")
      (node (ref "R18") (pin "2") (pinfunction "2_2") (pintype "passive"))
      (node (ref "X2") (pin "5") (pinfunction "KL_5") (pintype "passive"))
    )
    (net (code "65") (name "V+") (class "Default")
      (node (ref "C20") (pin "2") (pinfunction "2_2") (pintype "passive"))
      (node (ref "OK1") (pin "4") (pinfunction "COL_4") (pintype "passive"))
      (node (ref "OK2") (pin "4") (pinfunction "COL_4") (pintype "passive"))
      (node (ref "OK4") (pin "4") (pinfunction "COL_4") (pintype "passive"))
      (node (ref "X1") (pin "2") (pinfunction "KL_2") (pintype "passive"))
    )
    (net (code "66") (name "unconnected-(IC1B-OUT-Pad7)") (class "Default")
      (node (ref "IC1") (pin "7") (pinfunction "OUT_7") (pintype "output"))
    )
    (net (code "67") (name "unconnected-(IC2B-OUT-Pad7)") (class "Default")
      (node (ref "IC2") (pin "7") (pinfunction "OUT_7") (pintype "output"))
    )
    (net (code "68") (name "unconnected-(U2-EN-Pad3)") (class "Default")
      (node (ref "U2") (pin "3") (pinfunction "EN_3") (pintype "input"))
    )
  )
)
